# IGBT.net
KiCad netlist of a schematic drawn in Altium Designer
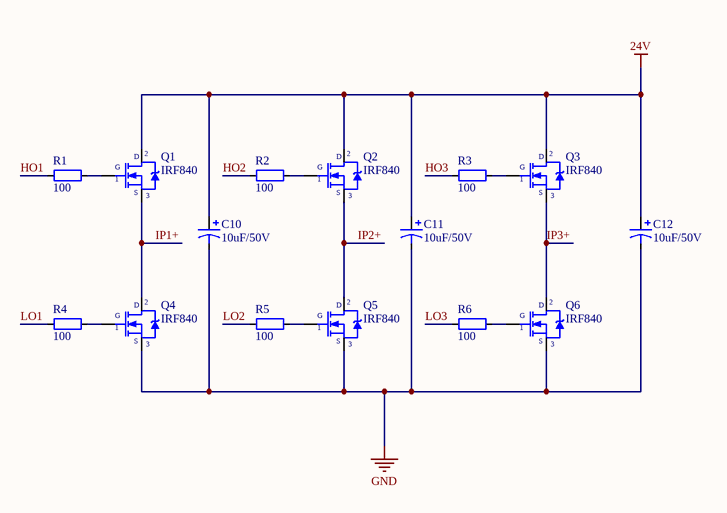
[diagram p0: IGBT.SchDoc]

(export (version "E")
  (design (tool "Eeschema 10.0.6"))
  (components
    (comp (ref "C10")
      (value "10uF/50V")
      (footprint "C3MM")
      (description "Polarized Capacitor (Axial)")
      (fields (field (name "PUBLISHER") "Altium Limited"))
      (libsource (lib "My Library_1") (part "Cap Pol"))
    )
    (comp (ref "C11")
      (value "10uF/50V")
      (footprint "C3MM")
      (description "Polarized Capacitor (Axial)")
      (fields (field (name "PUBLISHER") "Altium Limited"))
      (libsource (lib "My Library_1") (part "Cap Pol"))
    )
    (comp (ref "C12")
      (value "10uF/50V")
      (footprint "C3MM")
      (description "Polarized Capacitor (Axial)")
      (fields (field (name "PUBLISHER") "Altium Limited"))
      (libsource (lib "My Library_1") (part "Cap Pol"))
    )
    (comp (ref "Q1")
      (value "IRF840")
      (footprint "QTO-220")
      (description "MOSFET N - CHANNEL 500V - 0.75 - 8A - TO-220")
      (libsource (lib "My Library_1") (part "IRF840"))
    )
    (comp (ref "Q2")
      (value "IRF840")
      (footprint "QTO-220")
      (description "MOSFET N - CHANNEL 500V - 0.75 - 8A - TO-220")
      (libsource (lib "My Library_1") (part "IRF840"))
    )
    (comp (ref "Q3")
      (value "IRF840")
      (footprint "QTO-220")
      (description "MOSFET N - CHANNEL 500V - 0.75 - 8A - TO-220")
      (libsource (lib "My Library_1") (part "IRF840"))
    )
    (comp (ref "Q4")
      (value "IRF840")
      (footprint "QTO-220")
      (description "MOSFET N - CHANNEL 500V - 0.75 - 8A - TO-220")
      (libsource (lib "My Library_1") (part "IRF840"))
    )
    (comp (ref "Q5")
      (value "IRF840")
      (footprint "QTO-220")
      (description "MOSFET N - CHANNEL 500V - 0.75 - 8A - TO-220")
      (libsource (lib "My Library_1") (part "IRF840"))
    )
    (comp (ref "Q6")
      (value "IRF840")
      (footprint "QTO-220")
      (description "MOSFET N - CHANNEL 500V - 0.75 - 8A - TO-220")
      (libsource (lib "My Library_1") (part "IRF840"))
    )
    (comp (ref "R1")
      (value "100")
      (footprint "RES-SMD-0101")
      (description "Resistor")
      (fields
        (field (name "MANUFACTURER") "Generic Components")
        (field (name "PUBLISHER") "Altium Hobart Technology Centre")
      )
      (libsource (lib "My Library_1") (part "Resistor - SMD"))
    )
    (comp (ref "R2")
      (value "100")
      (footprint "RES-SMD-0101")
      (description "Resistor")
      (fields
        (field (name "MANUFACTURER") "Generic Components")
        (field (name "PUBLISHER") "Altium Hobart Technology Centre")
      )
      (libsource (lib "My Library_1") (part "Resistor - SMD"))
    )
    (comp (ref "R3")
      (value "100")
      (footprint "RES-SMD-0101")
      (description "Resistor")
      (fields
        (field (name "MANUFACTURER") "Generic Components")
        (field (name "PUBLISHER") "Altium Hobart Technology Centre")
      )
      (libsource (lib "My Library_1") (part "Resistor - SMD"))
    )
    (comp (ref "R4")
      (value "100")
      (footprint "RES-SMD-0101")
      (description "Resistor")
      (fields
        (field (name "MANUFACTURER") "Generic Components")
        (field (name "PUBLISHER") "Altium Hobart Technology Centre")
      )
      (libsource (lib "My Library_1") (part "Resistor - SMD"))
    )
    (comp (ref "R5")
      (value "100")
      (footprint "RES-SMD-0101")
      (description "Resistor")
      (fields
        (field (name "MANUFACTURER") "Generic Components")
        (field (name "PUBLISHER") "Altium Hobart Technology Centre")
      )
      (libsource (lib "My Library_1") (part "Resistor - SMD"))
    )
    (comp (ref "R6")
      (value "100")
      (footprint "RES-SMD-0101")
      (description "Resistor")
      (fields
        (field (name "MANUFACTURER") "Generic Components")
        (field (name "PUBLISHER") "Altium Hobart Technology Centre")
      )
      (libsource (lib "My Library_1") (part "Resistor - SMD"))
    )
  )
  (nets
    (net (code "1") (name "/HO1") (class "Default")
      (node (ref "R1") (pin "1") (pinfunction "1_1") (pintype "passive"))
    )
    (net (code "2") (name "/HO2") (class "Default")
      (node (ref "R2") (pin "1") (pinfunction "1_1") (pintype "passive"))
    )
    (net (code "3") (name "/HO3") (class "Default")
      (node (ref "R3") (pin "1") (pinfunction "1_1") (pintype "passive"))
    )
    (net (code "4") (name "/IP1+") (class "Default")
      (node (ref "Q1") (pin "3") (pinfunction "S_3") (pintype "passive"))
      (node (ref "Q4") (pin "2") (pinfunction "D_2") (pintype "passive"))
    )
    (net (code "5") (name "/IP2+") (class "Default")
      (node (ref "Q2") (pin "3") (pinfunction "S_3") (pintype "passive"))
      (node (ref "Q5") (pin "2") (pinfunction "D_2") (pintype "passive"))
    )
    (net (code "6") (name "/IP3+") (class "Default")
      (node (ref "Q3") (pin "3") (pinfunction "S_3") (pintype "passive"))
      (node (ref "Q6") (pin "2") (pinfunction "D_2") (pintype "passive"))
    )
    (net (code "7") (name "/LO1") (class "Default")
      (node (ref "R4") (pin "1") (pinfunction "1_1") (pintype "passive"))
    )
    (net (code "8") (name "/LO2") (class "Default")
      (node (ref "R5") (pin "1") (pinfunction "1_1") (pintype "passive"))
    )
    (net (code "9") (name "/LO3") (class "Default")
      (node (ref "R6") (pin "1") (pinfunction "1_1") (pintype "passive"))
    )
    (net (code "10") (name "24V") (class "Default")
      (node (ref "C10") (pin "1") (pinfunction "1_1") (pintype "passive"))
      (node (ref "C11") (pin "1") (pinfunction "1_1") (pintype "passive"))
      (node (ref "C12") (pin "1") (pinfunction "1_1") (pintype "passive"))
      (node (ref "Q1") (pin "2") (pinfunction "D_2") (pintype "passive"))
      (node (ref "Q2") (pin "2") (pinfunction "D_2") (pintype "passive"))
      (node (ref "Q3") (pin "2") (pinfunction "D_2") (pintype "passive"))
    )
    (net (code "11") (name "GND") (class "Default")
      (node (ref "C10") (pin "2") (pinfunction "2_2") (pintype "passive"))
      (node (ref "C11") (pin "2") (pinfunction "2_2") (pintype "passive"))
      (node (ref "C12") (pin "2") (pinfunction "2_2") (pintype "passive"))
      (node (ref "Q4") (pin "3") (pinfunction "S_3") (pintype "passive"))
      (node (ref "Q5") (pin "3") (pinfunction "S_3") (pintype "passive"))
      (node (ref "Q6") (pin "3") (pinfunction "S_3") (pintype "passive"))
    )
    (net (code "12") (name "Net-(Q1-G)") (class "Default")
      (node (ref "Q1") (pin "1") (pinfunction "G_1") (pintype "passive"))
      (node (ref "R1") (pin "2") (pinfunction "2_2") (pintype "passive"))
    )
    (net (code "13") (name "Net-(Q2-G)") (class "Default")
      (node (ref "Q2") (pin "1") (pinfunction "G_1") (pintype "passive"))
      (node (ref "R2") (pin "2") (pinfunction "2_2") (pintype "passive"))
    )
    (net (code "14") (name "Net-(Q3-G)") (class "Default")
      (node (ref "Q3") (pin "1") (pinfunction "G_1") (pintype "passive"))
      (node (ref "R3") (pin "2") (pinfunction "2_2") (pintype "passive"))
    )
    (net (code "15") (name "Net-(Q4-G)") (class "Default")
      (node (ref "Q4") (pin "1") (pinfunction "G_1") (pintype "passive"))
      (node (ref "R4") (pin "2") (pinfunction "2_2") (pintype "passive"))
    )
    (net (code "16") (name "Net-(Q5-G)") (class "Default")
      (node (ref "Q5") (pin "1") (pinfunction "G_1") (pintype "passive"))
      (node (ref "R5") (pin "2") (pinfunction "2_2") (pintype "passive"))
    )
    (net (code "17") (name "Net-(Q6-G)") (class "Default")
      (node (ref "Q6") (pin "1") (pinfunction "G_1") (pintype "passive"))
      (node (ref "R6") (pin "2") (pinfunction "2_2") (pintype "passive"))
    )
  )
)
